# hrobot.net
KiCad netlist of a schematic drawn in EAGLE
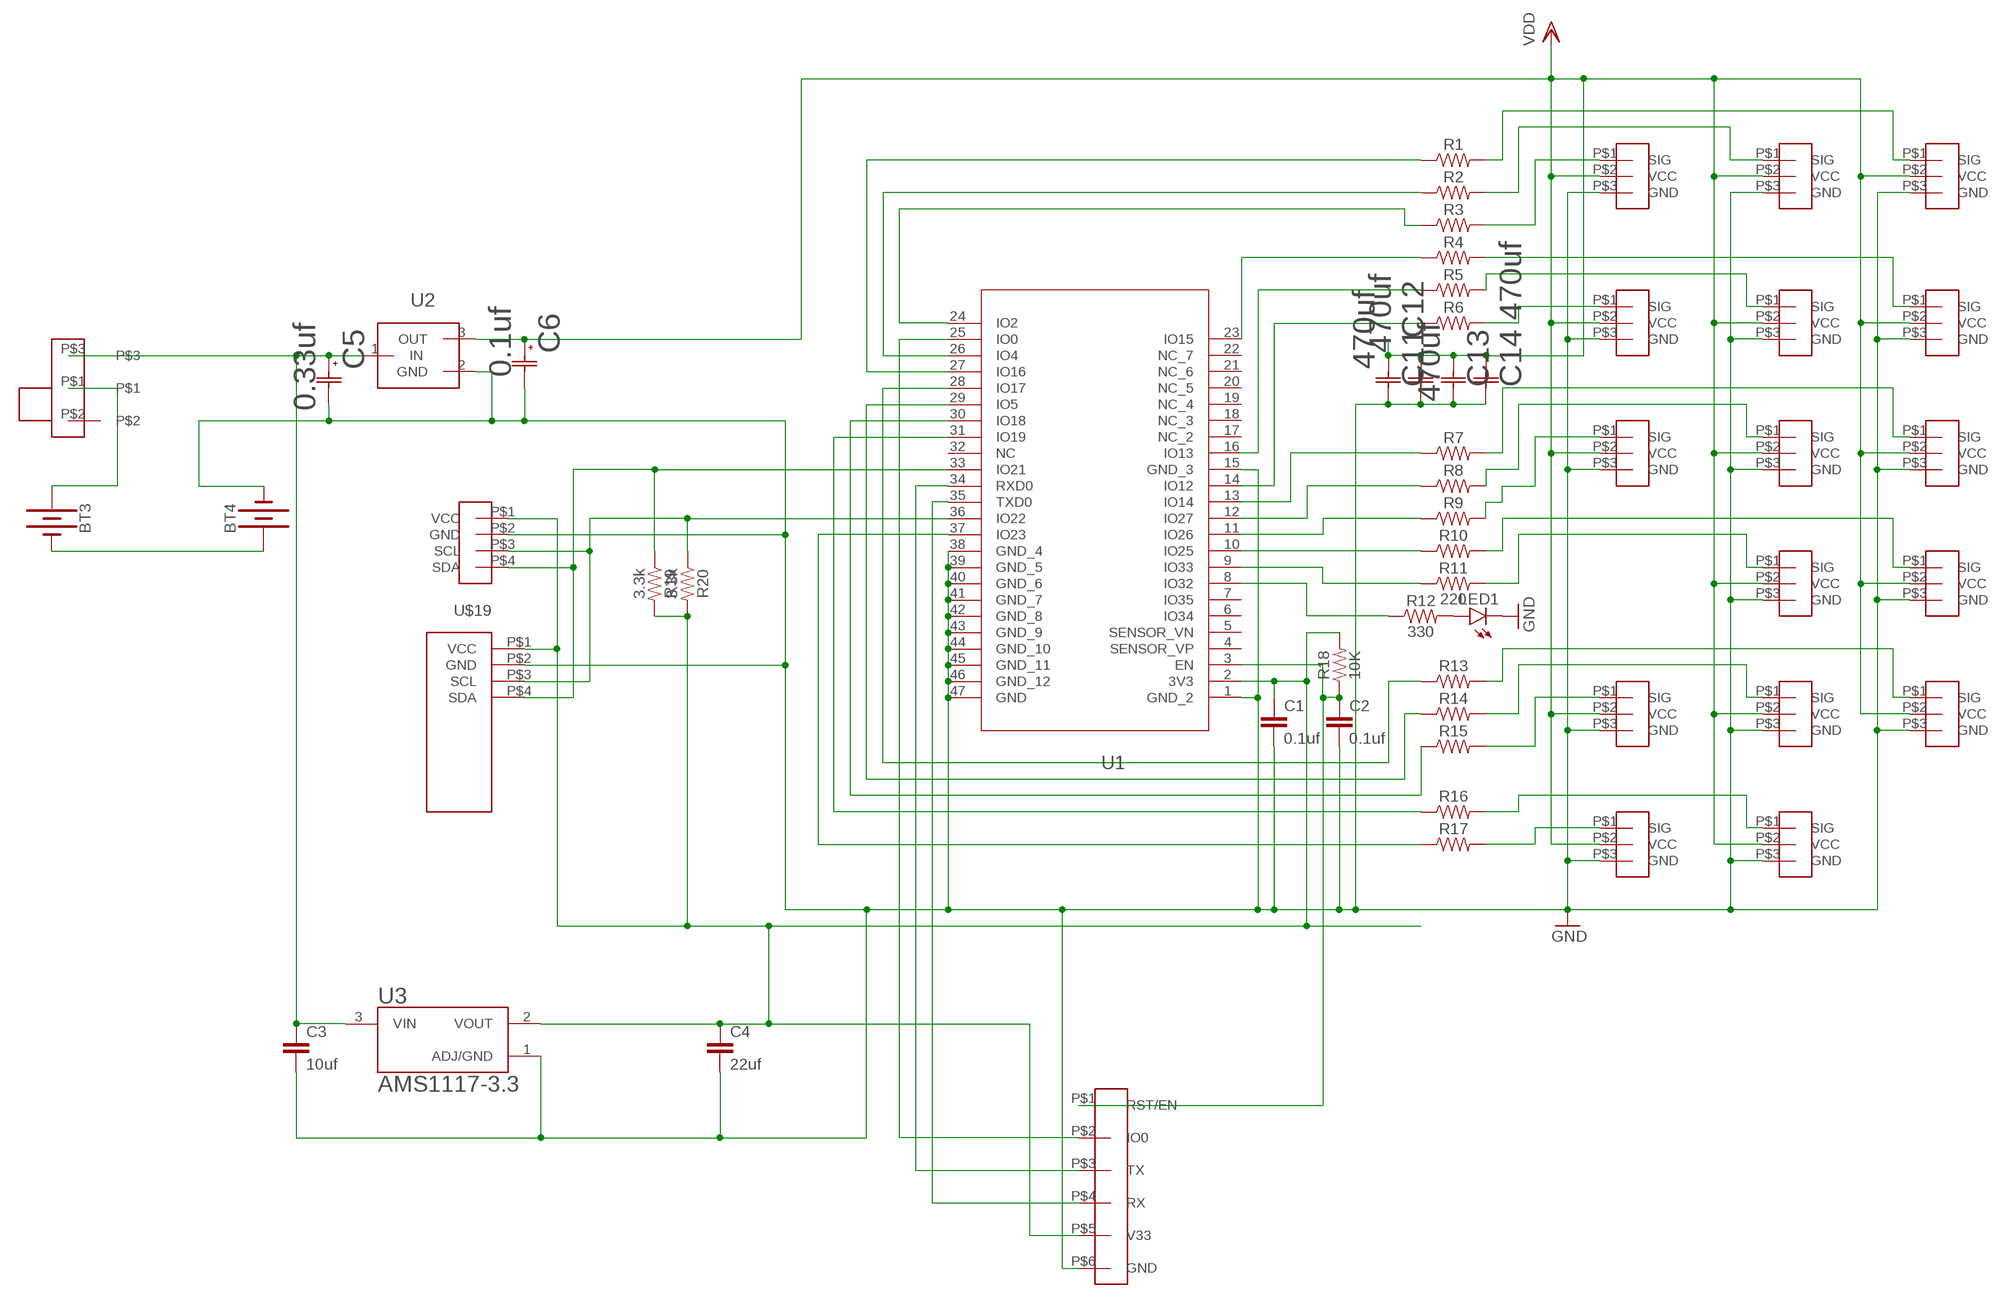
[diagram p0: schematic, sheet 1]

(export (version "E")
  (design (tool "Eeschema 10.0.6"))
  (components
    (comp (ref "BT3")
      (value "BATTERY-18650")
      (footprint "eagle-import:BATTERY_18650-HOLDER")
      (libsource (lib "eagle-import") (part "BATTERY-18650"))
    )
    (comp (ref "BT4")
      (value "BATTERY-18650")
      (footprint "eagle-import:BATTERY_18650-HOLDER")
      (libsource (lib "eagle-import") (part "BATTERY-18650"))
    )
    (comp (ref "C1")
      (value "0.1uf")
      (footprint "eagle-import:0805")
      (libsource (lib "eagle-import") (part "CAP-0805"))
    )
    (comp (ref "C2")
      (value "0.1uf")
      (footprint "eagle-import:0805")
      (libsource (lib "eagle-import") (part "CAP-0805"))
    )
    (comp (ref "C3")
      (value "10uf")
      (footprint "eagle-import:0805")
      (libsource (lib "eagle-import") (part "CAP-0805"))
    )
    (comp (ref "C4")
      (value "22uf")
      (footprint "eagle-import:0805")
      (libsource (lib "eagle-import") (part "CAP-0805"))
    )
    (comp (ref "C5")
      (value "0.33uf")
      (footprint "eagle-import:CAP_UWF_4X5P4_NCH")
      (fields
        (field (name "MANUFACTURER_PART_NUMBER") "UWP1HR33MCL1GB")
        (field (name "COPYRIGHT") "Copyright (C) 2025 Ultra Librarian. All rights reserved.")
      )
      (libsource (lib "eagle-import") (part "UWP1HR33MCL1GBCAP_UWF_4X5P4_NCH"))
    )
    (comp (ref "C6")
      (value "0.1uf")
      (footprint "eagle-import:CAP_UZE_4X3P9_NCH")
      (fields
        (field (name "MANUFACTURER_PART_NUMBER") "UZR1H0R1MCL1GB")
        (field (name "COPYRIGHT") "Copyright (C) 2025 Ultra Librarian. All rights reserved.")
      )
      (libsource (lib "eagle-import") (part "UZR1H0R1MCL1GBCAP_UZE_4X3P9_NCH"))
    )
    (comp (ref "C11")
      (value "470uf")
      (footprint "eagle-import:CAP_J-V_8X10P5_RUB")
      (fields
        (field (name "MANUFACTURER_PART_NUMBER") "16TZV470M8X10.5")
        (field (name "COPYRIGHT") "Copyright (C) 2024 Ultra Librarian. All rights reserved.")
      )
      (libsource (lib "eagle-import") (part "16TZV470M8X10.5CAP_J-V_8X10P5_RUB"))
    )
    (comp (ref "C12")
      (value "470uf")
      (footprint "eagle-import:CAP_J-V_8X10P5_RUB")
      (fields
        (field (name "MANUFACTURER_PART_NUMBER") "16TZV470M8X10.5")
        (field (name "COPYRIGHT") "Copyright (C) 2024 Ultra Librarian. All rights reserved.")
      )
      (libsource (lib "eagle-import") (part "16TZV470M8X10.5CAP_J-V_8X10P5_RUB"))
    )
    (comp (ref "C13")
      (value "470uf")
      (footprint "eagle-import:CAP_J-V_8X10P5_RUB")
      (fields
        (field (name "MANUFACTURER_PART_NUMBER") "16TZV470M8X10.5")
        (field (name "COPYRIGHT") "Copyright (C) 2024 Ultra Librarian. All rights reserved.")
      )
      (libsource (lib "eagle-import") (part "16TZV470M8X10.5CAP_J-V_8X10P5_RUB"))
    )
    (comp (ref "C14")
      (value "470uf")
      (footprint "eagle-import:CAP_J-V_8X10P5_RUB")
      (fields
        (field (name "MANUFACTURER_PART_NUMBER") "16TZV470M8X10.5")
        (field (name "COPYRIGHT") "Copyright (C) 2024 Ultra Librarian. All rights reserved.")
      )
      (libsource (lib "eagle-import") (part "16TZV470M8X10.5CAP_J-V_8X10P5_RUB"))
    )
    (comp (ref "LED1")
      (value "LEDSML0805")
      (footprint "eagle-import:SML0805")
      (libsource (lib "eagle-import") (part "LEDSML0805"))
    )
    (comp (ref "R1")
      (value "RESISTOR0805")
      (footprint "eagle-import:0805")
      (libsource (lib "eagle-import") (part "RESISTOR0805"))
    )
    (comp (ref "R2")
      (value "RESISTOR0805")
      (footprint "eagle-import:0805")
      (libsource (lib "eagle-import") (part "RESISTOR0805"))
    )
    (comp (ref "R3")
      (value "RESISTOR0805")
      (footprint "eagle-import:0805")
      (libsource (lib "eagle-import") (part "RESISTOR0805"))
    )
    (comp (ref "R4")
      (value "RESISTOR0805")
      (footprint "eagle-import:0805")
      (libsource (lib "eagle-import") (part "RESISTOR0805"))
    )
    (comp (ref "R5")
      (value "RESISTOR0805")
      (footprint "eagle-import:0805")
      (libsource (lib "eagle-import") (part "RESISTOR0805"))
    )
    (comp (ref "R6")
      (value "RESISTOR0805")
      (footprint "eagle-import:0805")
      (libsource (lib "eagle-import") (part "RESISTOR0805"))
    )
    (comp (ref "R7")
      (value "RESISTOR0805")
      (footprint "eagle-import:0805")
      (libsource (lib "eagle-import") (part "RESISTOR0805"))
    )
    (comp (ref "R8")
      (value "RESISTOR0805")
      (footprint "eagle-import:0805")
      (libsource (lib "eagle-import") (part "RESISTOR0805"))
    )
    (comp (ref "R9")
      (value "RESISTOR0805")
      (footprint "eagle-import:0805")
      (libsource (lib "eagle-import") (part "RESISTOR0805"))
    )
    (comp (ref "R10")
      (value "RESISTOR0805")
      (footprint "eagle-import:0805")
      (libsource (lib "eagle-import") (part "RESISTOR0805"))
    )
    (comp (ref "R11")
      (value "220")
      (footprint "eagle-import:0805")
      (libsource (lib "eagle-import") (part "RESISTOR0805"))
    )
    (comp (ref "R12")
      (value "330")
      (footprint "eagle-import:0805")
      (libsource (lib "eagle-import") (part "RESISTOR0805"))
    )
    (comp (ref "R13")
      (value "RESISTOR0805")
      (footprint "eagle-import:0805")
      (libsource (lib "eagle-import") (part "RESISTOR0805"))
    )
    (comp (ref "R14")
      (value "RESISTOR0805")
      (footprint "eagle-import:0805")
      (libsource (lib "eagle-import") (part "RESISTOR0805"))
    )
    (comp (ref "R15")
      (value "RESISTOR0805")
      (footprint "eagle-import:0805")
      (libsource (lib "eagle-import") (part "RESISTOR0805"))
    )
    (comp (ref "R16")
      (value "RESISTOR0805")
      (footprint "eagle-import:0805")
      (libsource (lib "eagle-import") (part "RESISTOR0805"))
    )
    (comp (ref "R17")
      (value "RESISTOR0805")
      (footprint "eagle-import:0805")
      (libsource (lib "eagle-import") (part "RESISTOR0805"))
    )
    (comp (ref "R18")
      (value "10K")
      (footprint "eagle-import:0805")
      (libsource (lib "eagle-import") (part "RESISTOR0805"))
    )
    (comp (ref "R19")
      (value "3.3k")
      (footprint "eagle-import:0805")
      (libsource (lib "eagle-import") (part "RESISTOR0805"))
    )
    (comp (ref "R20")
      (value "3.3k")
      (footprint "eagle-import:0805")
      (libsource (lib "eagle-import") (part "RESISTOR0805"))
    )
    (comp (ref "U$1")
      (value "SERVO")
      (footprint "eagle-import:3PINS")
      (libsource (lib "eagle-import") (part "SERVO"))
    )
    (comp (ref "U$2")
      (value "SERVO")
      (footprint "eagle-import:3PINS")
      (libsource (lib "eagle-import") (part "SERVO"))
    )
    (comp (ref "U$3")
      (value "SERVO")
      (footprint "eagle-import:3PINS")
      (libsource (lib "eagle-import") (part "SERVO"))
    )
    (comp (ref "U$5")
      (value "SERVO")
      (footprint "eagle-import:3PINS")
      (libsource (lib "eagle-import") (part "SERVO"))
    )
    (comp (ref "U$6")
      (value "SERVO")
      (footprint "eagle-import:3PINS")
      (libsource (lib "eagle-import") (part "SERVO"))
    )
    (comp (ref "U$7")
      (value "SERVO")
      (footprint "eagle-import:3PINS")
      (libsource (lib "eagle-import") (part "SERVO"))
    )
    (comp (ref "U$8")
      (value "SERVO")
      (footprint "eagle-import:3PINS")
      (libsource (lib "eagle-import") (part "SERVO"))
    )
    (comp (ref "U$9")
      (value "SERVO")
      (footprint "eagle-import:3PINS")
      (libsource (lib "eagle-import") (part "SERVO"))
    )
    (comp (ref "U$10")
      (value "SERVO")
      (footprint "eagle-import:3PINS")
      (libsource (lib "eagle-import") (part "SERVO"))
    )
    (comp (ref "U$11")
      (value "SERVO")
      (footprint "eagle-import:3PINS")
      (libsource (lib "eagle-import") (part "SERVO"))
    )
    (comp (ref "U$12")
      (value "SERVO")
      (footprint "eagle-import:3PINS")
      (libsource (lib "eagle-import") (part "SERVO"))
    )
    (comp (ref "U$13")
      (value "SERVO")
      (footprint "eagle-import:3PINS")
      (libsource (lib "eagle-import") (part "SERVO"))
    )
    (comp (ref "U$14")
      (value "SERVO")
      (footprint "eagle-import:3PINS")
      (libsource (lib "eagle-import") (part "SERVO"))
    )
    (comp (ref "U$15")
      (value "SERVO")
      (footprint "eagle-import:3PINS")
      (libsource (lib "eagle-import") (part "SERVO"))
    )
    (comp (ref "U$16")
      (value "SERVO")
      (footprint "eagle-import:3PINS")
      (libsource (lib "eagle-import") (part "SERVO"))
    )
    (comp (ref "U$17")
      (value "SERVO")
      (footprint "eagle-import:3PINS")
      (libsource (lib "eagle-import") (part "SERVO"))
    )
    (comp (ref "U$18")
      (value "OLEDVCC")
      (footprint "eagle-import:OLEPINS")
      (libsource (lib "eagle-import") (part "OLEDVCC"))
    )
    (comp (ref "U$19")
      (value "GYRO")
      (footprint "eagle-import:4PINS")
      (libsource (lib "eagle-import") (part "GYRO"))
    )
    (comp (ref "U$20")
      (value "PWR3PINS")
      (footprint "eagle-import:PWR3PINS")
      (libsource (lib "eagle-import") (part "PWR3PINS"))
    )
    (comp (ref "U$23")
      (value "USBCOUT")
      (footprint "eagle-import:6PINS")
      (libsource (lib "eagle-import") (part "USBCOUT"))
    )
    (comp (ref "U1")
      (value "ESP32-WROOM-32E_(4MB)ESP32�WROOM�32E_EXP")
      (footprint "eagle-import:ESP32�WROOM�32E_EXP")
      (fields
        (field (name "MANUFACTURER_PART_NUMBER") "ESP32-WROOM-32E (4MB)")
        (field (name "COPYRIGHT") "Copyright (C) 2024 Ultra Librarian. All rights reserved.")
      )
      (libsource (lib "eagle-import") (part "ESP32-WROOM-32E_(4MB)ESP32�WROOM�32E_EXP"))
    )
    (comp (ref "U2")
      (value "L7806")
      (footprint "eagle-import:L7805FOOT")
      (libsource (lib "eagle-import") (part "L7805"))
    )
    (comp (ref "U3")
      (value "AMS1117-3.3")
      (footprint "eagle-import:SOT229P700X180-4N")
      (fields (field (name "MF") "Advanced Monolithic Systems"))
      (libsource (lib "eagle-import") (part "AMS1117-3.3"))
    )
  )
  (nets
    (net (code "1") (name "GND") (class "Default")
      (node (ref "BT4") (pin "GND@1") (pinfunction "-_GND@1") (pintype "power_in"))
      (node (ref "C1") (pin "2") (pinfunction "2_2") (pintype "passive"))
      (node (ref "C11") (pin "2") (pinfunction "2_2") (pintype "passive"))
      (node (ref "C12") (pin "2") (pinfunction "2_2") (pintype "passive"))
      (node (ref "C13") (pin "2") (pinfunction "2_2") (pintype "passive"))
      (node (ref "C14") (pin "2") (pinfunction "2_2") (pintype "passive"))
      (node (ref "C2") (pin "2") (pinfunction "2_2") (pintype "passive"))
      (node (ref "C3") (pin "2") (pinfunction "2_2") (pintype "passive"))
      (node (ref "C4") (pin "2") (pinfunction "2_2") (pintype "passive"))
      (node (ref "C5") (pin "2") (pinfunction "2_2") (pintype "passive"))
      (node (ref "C6") (pin "2") (pinfunction "2_2") (pintype "passive"))
      (node (ref "LED1") (pin "C") (pinfunction "C_C") (pintype "passive"))
      (node (ref "U$1") (pin "P$3") (pinfunction "GND_P$3") (pintype "bidirectional"))
      (node (ref "U$10") (pin "P$3") (pinfunction "GND_P$3") (pintype "bidirectional"))
      (node (ref "U$11") (pin "P$3") (pinfunction "GND_P$3") (pintype "bidirectional"))
      (node (ref "U$12") (pin "P$3") (pinfunction "GND_P$3") (pintype "bidirectional"))
      (node (ref "U$13") (pin "P$3") (pinfunction "GND_P$3") (pintype "bidirectional"))
      (node (ref "U$14") (pin "P$3") (pinfunction "GND_P$3") (pintype "bidirectional"))
      (node (ref "U$15") (pin "P$3") (pinfunction "GND_P$3") (pintype "bidirectional"))
      (node (ref "U$16") (pin "P$3") (pinfunction "GND_P$3") (pintype "bidirectional"))
      (node (ref "U$17") (pin "P$3") (pinfunction "GND_P$3") (pintype "bidirectional"))
      (node (ref "U$18") (pin "P$2") (pinfunction "GND_P$2") (pintype "bidirectional"))
      (node (ref "U$19") (pin "P$2") (pinfunction "GND_P$2") (pintype "power_in"))
      (node (ref "U$2") (pin "P$3") (pinfunction "GND_P$3") (pintype "bidirectional"))
      (node (ref "U$23") (pin "P$6") (pinfunction "GND_P$6") (pintype "bidirectional"))
      (node (ref "U$3") (pin "P$3") (pinfunction "GND_P$3") (pintype "bidirectional"))
      (node (ref "U$5") (pin "P$3") (pinfunction "GND_P$3") (pintype "bidirectional"))
      (node (ref "U$6") (pin "P$3") (pinfunction "GND_P$3") (pintype "bidirectional"))
      (node (ref "U$7") (pin "P$3") (pinfunction "GND_P$3") (pintype "bidirectional"))
      (node (ref "U$8") (pin "P$3") (pinfunction "GND_P$3") (pintype "bidirectional"))
      (node (ref "U$9") (pin "P$3") (pinfunction "GND_P$3") (pintype "bidirectional"))
      (node (ref "U1") (pin "1") (pinfunction "GND_2_1") (pintype "passive"))
      (node (ref "U1") (pin "15") (pinfunction "GND_3_15") (pintype "passive"))
      (node (ref "U1") (pin "38") (pinfunction "GND_4_38") (pintype "passive"))
      (node (ref "U1") (pin "39") (pinfunction "GND_5_39") (pintype "passive"))
      (node (ref "U1") (pin "40") (pinfunction "GND_6_40") (pintype "passive"))
      (node (ref "U1") (pin "41") (pinfunction "GND_7_41") (pintype "passive"))
      (node (ref "U1") (pin "42") (pinfunction "GND_8_42") (pintype "passive"))
      (node (ref "U1") (pin "43") (pinfunction "GND_9_43") (pintype "passive"))
      (node (ref "U1") (pin "44") (pinfunction "GND_10_44") (pintype "passive"))
      (node (ref "U1") (pin "45") (pinfunction "GND_11_45") (pintype "passive"))
      (node (ref "U1") (pin "46") (pinfunction "GND_12_46") (pintype "passive"))
      (node (ref "U1") (pin "47") (pinfunction "GND_47") (pintype "passive"))
      (node (ref "U2") (pin "2") (pinfunction "GND_2") (pintype "bidirectional"))
      (node (ref "U3") (pin "1") (pinfunction "ADJ/GND_1") (pintype "power_in"))
    )
    (net (code "2") (name "Net-(BT3-+)") (class "Default")
      (node (ref "BT3") (pin "PWR@1") (pinfunction "+_PWR@1") (pintype "power_in"))
      (node (ref "U$20") (pin "P$1") (pinfunction "P$1_P$1") (pintype "bidirectional"))
    )
    (net (code "3") (name "Net-(BT3--)") (class "Default")
      (node (ref "BT3") (pin "GND@1") (pinfunction "-_GND@1") (pintype "power_in"))
      (node (ref "BT4") (pin "PWR@1") (pinfunction "+_PWR@1") (pintype "power_in"))
    )
    (net (code "4") (name "Net-(LED1-PadA)") (class "Default")
      (node (ref "LED1") (pin "A") (pinfunction "A_A") (pintype "passive"))
      (node (ref "R12") (pin "2") (pinfunction "2_2") (pintype "passive"))
    )
    (net (code "5") (name "Net-(U$1-SIG)") (class "Default")
      (node (ref "R3") (pin "2") (pinfunction "2_2") (pintype "passive"))
      (node (ref "U$1") (pin "P$1") (pinfunction "SIG_P$1") (pintype "bidirectional"))
    )
    (net (code "6") (name "Net-(U$2-SIG)") (class "Default")
      (node (ref "R6") (pin "2") (pinfunction "2_2") (pintype "passive"))
      (node (ref "U$2") (pin "P$1") (pinfunction "SIG_P$1") (pintype "bidirectional"))
    )
    (net (code "7") (name "Net-(U$3-SIG)") (class "Default")
      (node (ref "R9") (pin "2") (pinfunction "2_2") (pintype "passive"))
      (node (ref "U$3") (pin "P$1") (pinfunction "SIG_P$1") (pintype "bidirectional"))
    )
    (net (code "8") (name "Net-(U$5-SIG)") (class "Default")
      (node (ref "R15") (pin "2") (pinfunction "2_2") (pintype "passive"))
      (node (ref "U$5") (pin "P$1") (pinfunction "SIG_P$1") (pintype "bidirectional"))
    )
    (net (code "9") (name "Net-(U$6-SIG)") (class "Default")
      (node (ref "R17") (pin "2") (pinfunction "2_2") (pintype "passive"))
      (node (ref "U$6") (pin "P$1") (pinfunction "SIG_P$1") (pintype "bidirectional"))
    )
    (net (code "10") (name "Net-(U$7-SIG)") (class "Default")
      (node (ref "R2") (pin "2") (pinfunction "2_2") (pintype "passive"))
      (node (ref "U$7") (pin "P$1") (pinfunction "SIG_P$1") (pintype "bidirectional"))
    )
    (net (code "11") (name "Net-(U$8-SIG)") (class "Default")
      (node (ref "R5") (pin "2") (pinfunction "2_2") (pintype "passive"))
      (node (ref "U$8") (pin "P$1") (pinfunction "SIG_P$1") (pintype "bidirectional"))
    )
    (net (code "12") (name "Net-(U$9-SIG)") (class "Default")
      (node (ref "R8") (pin "2") (pinfunction "2_2") (pintype "passive"))
      (node (ref "U$9") (pin "P$1") (pinfunction "SIG_P$1") (pintype "bidirectional"))
    )
    (net (code "13") (name "Net-(U$10-SIG)") (class "Default")
      (node (ref "R11") (pin "2") (pinfunction "2_2") (pintype "passive"))
      (node (ref "U$10") (pin "P$1") (pinfunction "SIG_P$1") (pintype "bidirectional"))
    )
    (net (code "14") (name "Net-(U$11-SIG)") (class "Default")
      (node (ref "R14") (pin "2") (pinfunction "2_2") (pintype "passive"))
      (node (ref "U$11") (pin "P$1") (pinfunction "SIG_P$1") (pintype "bidirectional"))
    )
    (net (code "15") (name "Net-(U$12-SIG)") (class "Default")
      (node (ref "R16") (pin "2") (pinfunction "2_2") (pintype "passive"))
      (node (ref "U$12") (pin "P$1") (pinfunction "SIG_P$1") (pintype "bidirectional"))
    )
    (net (code "16") (name "Net-(U$13-SIG)") (class "Default")
      (node (ref "R1") (pin "2") (pinfunction "2_2") (pintype "passive"))
      (node (ref "U$13") (pin "P$1") (pinfunction "SIG_P$1") (pintype "bidirectional"))
    )
    (net (code "17") (name "Net-(U$14-SIG)") (class "Default")
      (node (ref "R4") (pin "2") (pinfunction "2_2") (pintype "passive"))
      (node (ref "U$14") (pin "P$1") (pinfunction "SIG_P$1") (pintype "bidirectional"))
    )
    (net (code "18") (name "Net-(U$15-SIG)") (class "Default")
      (node (ref "R7") (pin "2") (pinfunction "2_2") (pintype "passive"))
      (node (ref "U$15") (pin "P$1") (pinfunction "SIG_P$1") (pintype "bidirectional"))
    )
    (net (code "19") (name "Net-(U$16-SIG)") (class "Default")
      (node (ref "R10") (pin "2") (pinfunction "2_2") (pintype "passive"))
      (node (ref "U$16") (pin "P$1") (pinfunction "SIG_P$1") (pintype "bidirectional"))
    )
    (net (code "20") (name "Net-(U$17-SIG)") (class "Default")
      (node (ref "R13") (pin "2") (pinfunction "2_2") (pintype "passive"))
      (node (ref "U$17") (pin "P$1") (pinfunction "SIG_P$1") (pintype "bidirectional"))
    )
    (net (code "21") (name "Net-(U$18-SCL)") (class "Default")
      (node (ref "R20") (pin "1") (pinfunction "1_1") (pintype "passive"))
      (node (ref "U$18") (pin "P$3") (pinfunction "SCL_P$3") (pintype "bidirectional"))
      (node (ref "U$19") (pin "P$3") (pinfunction "SCL_P$3") (pintype "bidirectional"))
      (node (ref "U1") (pin "36") (pinfunction "IO22_36") (pintype "bidirectional"))
    )
    (net (code "22") (name "Net-(U$18-SDA)") (class "Default")
      (node (ref "R19") (pin "1") (pinfunction "1_1") (pintype "passive"))
      (node (ref "U$18") (pin "P$4") (pinfunction "SDA_P$4") (pintype "bidirectional"))
      (node (ref "U$19") (pin "P$4") (pinfunction "SDA_P$4") (pintype "bidirectional"))
      (node (ref "U1") (pin "33") (pinfunction "IO21_33") (pintype "bidirectional"))
    )
    (net (code "23") (name "Net-(U$18-VCC)") (class "Default")
      (node (ref "C1") (pin "1") (pinfunction "1_1") (pintype "passive"))
      (node (ref "C4") (pin "1") (pinfunction "1_1") (pintype "passive"))
      (node (ref "R18") (pin "2") (pinfunction "2_2") (pintype "passive"))
      (node (ref "R19") (pin "2") (pinfunction "2_2") (pintype "passive"))
      (node (ref "R20") (pin "2") (pinfunction "2_2") (pintype "passive"))
      (node (ref "U$18") (pin "P$1") (pinfunction "VCC_P$1") (pintype "bidirectional"))
      (node (ref "U$19") (pin "P$1") (pinfunction "VCC_P$1") (pintype "power_in"))
      (node (ref "U$23") (pin "P$5") (pinfunction "V33_P$5") (pintype "bidirectional"))
      (node (ref "U1") (pin "2") (pinfunction "3V3_2") (pintype "power_in"))
      (node (ref "U3") (pin "2") (pinfunction "VOUT_2") (pintype "output"))
    )
    (net (code "24") (name "Net-(U$23-IO0)") (class "Default")
      (node (ref "U$23") (pin "P$2") (pinfunction "IO0_P$2") (pintype "bidirectional"))
      (node (ref "U1") (pin "25") (pinfunction "IO0_25") (pintype "bidirectional"))
    )
    (net (code "25") (name "Net-(U$23-RST{slash}EN)") (class "Default")
      (node (ref "C2") (pin "1") (pinfunction "1_1") (pintype "passive"))
      (node (ref "R18") (pin "1") (pinfunction "1_1") (pintype "passive"))
      (node (ref "U$23") (pin "P$1") (pinfunction "RST/EN_P$1") (pintype "bidirectional"))
      (node (ref "U1") (pin "3") (pinfunction "EN_3") (pintype "input"))
    )
    (net (code "26") (name "Net-(U$23-RX)") (class "Default")
      (node (ref "U$23") (pin "P$4") (pinfunction "RX_P$4") (pintype "bidirectional"))
      (node (ref "U1") (pin "35") (pinfunction "TXD0_35") (pintype "bidirectional"))
    )
    (net (code "27") (name "Net-(U$23-TX)") (class "Default")
      (node (ref "U$23") (pin "P$3") (pinfunction "TX_P$3") (pintype "bidirectional"))
      (node (ref "U1") (pin "34") (pinfunction "RXD0_34") (pintype "bidirectional"))
    )
    (net (code "28") (name "Net-(U1-IO2)") (class "Default")
      (node (ref "R3") (pin "1") (pinfunction "1_1") (pintype "passive"))
      (node (ref "U1") (pin "24") (pinfunction "IO2_24") (pintype "bidirectional"))
    )
    (net (code "29") (name "Net-(U1-IO4)") (class "Default")
      (node (ref "R2") (pin "1") (pinfunction "1_1") (pintype "passive"))
      (node (ref "U1") (pin "26") (pinfunction "IO4_26") (pintype "bidirectional"))
    )
    (net (code "30") (name "Net-(U1-IO5)") (class "Default")
      (node (ref "R14") (pin "1") (pinfunction "1_1") (pintype "passive"))
      (node (ref "U1") (pin "29") (pinfunction "IO5_29") (pintype "bidirectional"))
    )
    (net (code "31") (name "Net-(U1-IO12)") (class "Default")
      (node (ref "R6") (pin "1") (pinfunction "1_1") (pintype "passive"))
      (node (ref "U1") (pin "14") (pinfunction "IO12_14") (pintype "bidirectional"))
    )
    (net (code "32") (name "Net-(U1-IO13)") (class "Default")
      (node (ref "R5") (pin "1") (pinfunction "1_1") (pintype "passive"))
      (node (ref "U1") (pin "16") (pinfunction "IO13_16") (pintype "bidirectional"))
    )
    (net (code "33") (name "Net-(U1-IO14)") (class "Default")
      (node (ref "R7") (pin "1") (pinfunction "1_1") (pintype "passive"))
      (node (ref "U1") (pin "13") (pinfunction "IO14_13") (pintype "bidirectional"))
    )
    (net (code "34") (name "Net-(U1-IO15)") (class "Default")
      (node (ref "R4") (pin "1") (pinfunction "1_1") (pintype "passive"))
      (node (ref "U1") (pin "23") (pinfunction "IO15_23") (pintype "bidirectional"))
    )
    (net (code "35") (name "Net-(U1-IO16)") (class "Default")
      (node (ref "R1") (pin "1") (pinfunction "1_1") (pintype "passive"))
      (node (ref "U1") (pin "27") (pinfunction "IO16_27") (pintype "bidirectional"))
    )
    (net (code "36") (name "Net-(U1-IO17)") (class "Default")
      (node (ref "R13") (pin "1") (pinfunction "1_1") (pintype "passive"))
      (node (ref "U1") (pin "28") (pinfunction "IO17_28") (pintype "bidirectional"))
    )
    (net (code "37") (name "Net-(U1-IO18)") (class "Default")
      (node (ref "R15") (pin "1") (pinfunction "1_1") (pintype "passive"))
      (node (ref "U1") (pin "30") (pinfunction "IO18_30") (pintype "bidirectional"))
    )
    (net (code "38") (name "Net-(U1-IO19)") (class "Default")
      (node (ref "R16") (pin "1") (pinfunction "1_1") (pintype "passive"))
      (node (ref "U1") (pin "31") (pinfunction "IO19_31") (pintype "bidirectional"))
    )
    (net (code "39") (name "Net-(U1-IO23)") (class "Default")
      (node (ref "R17") (pin "1") (pinfunction "1_1") (pintype "passive"))
      (node (ref "U1") (pin "37") (pinfunction "IO23_37") (pintype "bidirectional"))
    )
    (net (code "40") (name "Net-(U1-IO25)") (class "Default")
      (node (ref "R10") (pin "1") (pinfunction "1_1") (pintype "passive"))
      (node (ref "U1") (pin "10") (pinfunction "IO25_10") (pintype "bidirectional"))
    )
    (net (code "41") (name "Net-(U1-IO26)") (class "Default")
      (node (ref "R9") (pin "1") (pinfunction "1_1") (pintype "passive"))
      (node (ref "U1") (pin "11") (pinfunction "IO26_11") (pintype "bidirectional"))
    )
    (net (code "42") (name "Net-(U1-IO27)") (class "Default")
      (node (ref "R8") (pin "1") (pinfunction "1_1") (pintype "passive"))
      (node (ref "U1") (pin "12") (pinfunction "IO27_12") (pintype "bidirectional"))
    )
    (net (code "43") (name "Net-(U1-IO32)") (class "Default")
      (node (ref "R12") (pin "1") (pinfunction "1_1") (pintype "passive"))
      (node (ref "U1") (pin "8") (pinfunction "IO32_8") (pintype "bidirectional"))
    )
    (net (code "44") (name "Net-(U1-IO33)") (class "Default")
      (node (ref "R11") (pin "1") (pinfunction "1_1") (pintype "passive"))
      (node (ref "U1") (pin "9") (pinfunction "IO33_9") (pintype "bidirectional"))
    )
    (net (code "45") (name "Net-(U2-IN)") (class "Default")
      (node (ref "C3") (pin "1") (pinfunction "1_1") (pintype "passive"))
      (node (ref "C5") (pin "1") (pinfunction "1_1") (pintype "passive"))
      (node (ref "U$20") (pin "P$3") (pinfunction "P$3_P$3") (pintype "bidirectional"))
      (node (ref "U2") (pin "1") (pinfunction "IN_1") (pintype "bidirectional"))
      (node (ref "U3") (pin "3") (pinfunction "VIN_3") (pintype "input"))
    )
    (net (code "46") (name "VDD") (class "Default")
      (node (ref "C11") (pin "1") (pinfunction "1_1") (pintype "passive"))
      (node (ref "C12") (pin "1") (pinfunction "1_1") (pintype "passive"))
      (node (ref "C13") (pin "1") (pinfunction "1_1") (pintype "passive"))
      (node (ref "C14") (pin "1") (pinfunction "1_1") (pintype "passive"))
      (node (ref "C6") (pin "1") (pinfunction "1_1") (pintype "passive"))
      (node (ref "U$1") (pin "P$2") (pinfunction "VCC_P$2") (pintype "bidirectional"))
      (node (ref "U$10") (pin "P$2") (pinfunction "VCC_P$2") (pintype "bidirectional"))
      (node (ref "U$11") (pin "P$2") (pinfunction "VCC_P$2") (pintype "bidirectional"))
      (node (ref "U$12") (pin "P$2") (pinfunction "VCC_P$2") (pintype "bidirectional"))
      (node (ref "U$13") (pin "P$2") (pinfunction "VCC_P$2") (pintype "bidirectional"))
      (node (ref "U$14") (pin "P$2") (pinfunction "VCC_P$2") (pintype "bidirectional"))
      (node (ref "U$15") (pin "P$2") (pinfunction "VCC_P$2") (pintype "bidirectional"))
      (node (ref "U$16") (pin "P$2") (pinfunction "VCC_P$2") (pintype "bidirectional"))
      (node (ref "U$17") (pin "P$2") (pinfunction "VCC_P$2") (pintype "bidirectional"))
      (node (ref "U$2") (pin "P$2") (pinfunction "VCC_P$2") (pintype "bidirectional"))
      (node (ref "U$3") (pin "P$2") (pinfunction "VCC_P$2") (pintype "bidirectional"))
      (node (ref "U$5") (pin "P$2") (pinfunction "VCC_P$2") (pintype "bidirectional"))
      (node (ref "U$6") (pin "P$2") (pinfunction "VCC_P$2") (pintype "bidirectional"))
      (node (ref "U$7") (pin "P$2") (pinfunction "VCC_P$2") (pintype "bidirectional"))
      (node (ref "U$8") (pin "P$2") (pinfunction "VCC_P$2") (pintype "bidirectional"))
      (node (ref "U$9") (pin "P$2") (pinfunction "VCC_P$2") (pintype "bidirectional"))
      (node (ref "U2") (pin "3") (pinfunction "OUT_3") (pintype "bidirectional"))
    )
    (net (code "47") (name "unconnected-(U$20-PadP$2)") (class "Default")
      (node (ref "U$20") (pin "P$2") (pinfunction "P$2_P$2") (pintype "bidirectional"))
    )
    (net (code "48") (name "unconnected-(U1-IO34-Pad6)") (class "Default")
      (node (ref "U1") (pin "6") (pinfunction "IO34_6") (pintype "input"))
    )
    (net (code "49") (name "unconnected-(U1-IO35-Pad7)") (class "Default")
      (node (ref "U1") (pin "7") (pinfunction "IO35_7") (pintype "input"))
    )
    (net (code "50") (name "unconnected-(U1-NC-Pad32)") (class "Default")
      (node (ref "U1") (pin "32") (pinfunction "NC_32") (pintype "no_connect"))
    )
    (net (code "51") (name "unconnected-(U1-NC_2-Pad17)") (class "Default")
      (node (ref "U1") (pin "17") (pinfunction "NC_2_17") (pintype "no_connect"))
    )
    (net (code "52") (name "unconnected-(U1-NC_3-Pad18)") (class "Default")
      (node (ref "U1") (pin "18") (pinfunction "NC_3_18") (pintype "no_connect"))
    )
    (net (code "53") (name "unconnected-(U1-NC_4-Pad19)") (class "Default")
      (node (ref "U1") (pin "19") (pinfunction "NC_4_19") (pintype "no_connect"))
    )
    (net (code "54") (name "unconnected-(U1-NC_5-Pad20)") (class "Default")
      (node (ref "U1") (pin "20") (pinfunction "NC_5_20") (pintype "no_connect"))
    )
    (net (code "55") (name "unconnected-(U1-NC_6-Pad21)") (class "Default")
      (node (ref "U1") (pin "21") (pinfunction "NC_6_21") (pintype "no_connect"))
    )
    (net (code "56") (name "unconnected-(U1-NC_7-Pad22)") (class "Default")
      (node (ref "U1") (pin "22") (pinfunction "NC_7_22") (pintype "no_connect"))
    )
    (net (code "57") (name "unconnected-(U1-SENSOR_VN-Pad5)") (class "Default")
      (node (ref "U1") (pin "5") (pinfunction "SENSOR_VN_5") (pintype "input"))
    )
    (net (code "58") (name "unconnected-(U1-SENSOR_VP-Pad4)") (class "Default")
      (node (ref "U1") (pin "4") (pinfunction "SENSOR_VP_4") (pintype "input"))
    )
  )
)
